# rev11.net
KiCad netlist of a schematic drawn in EAGLE
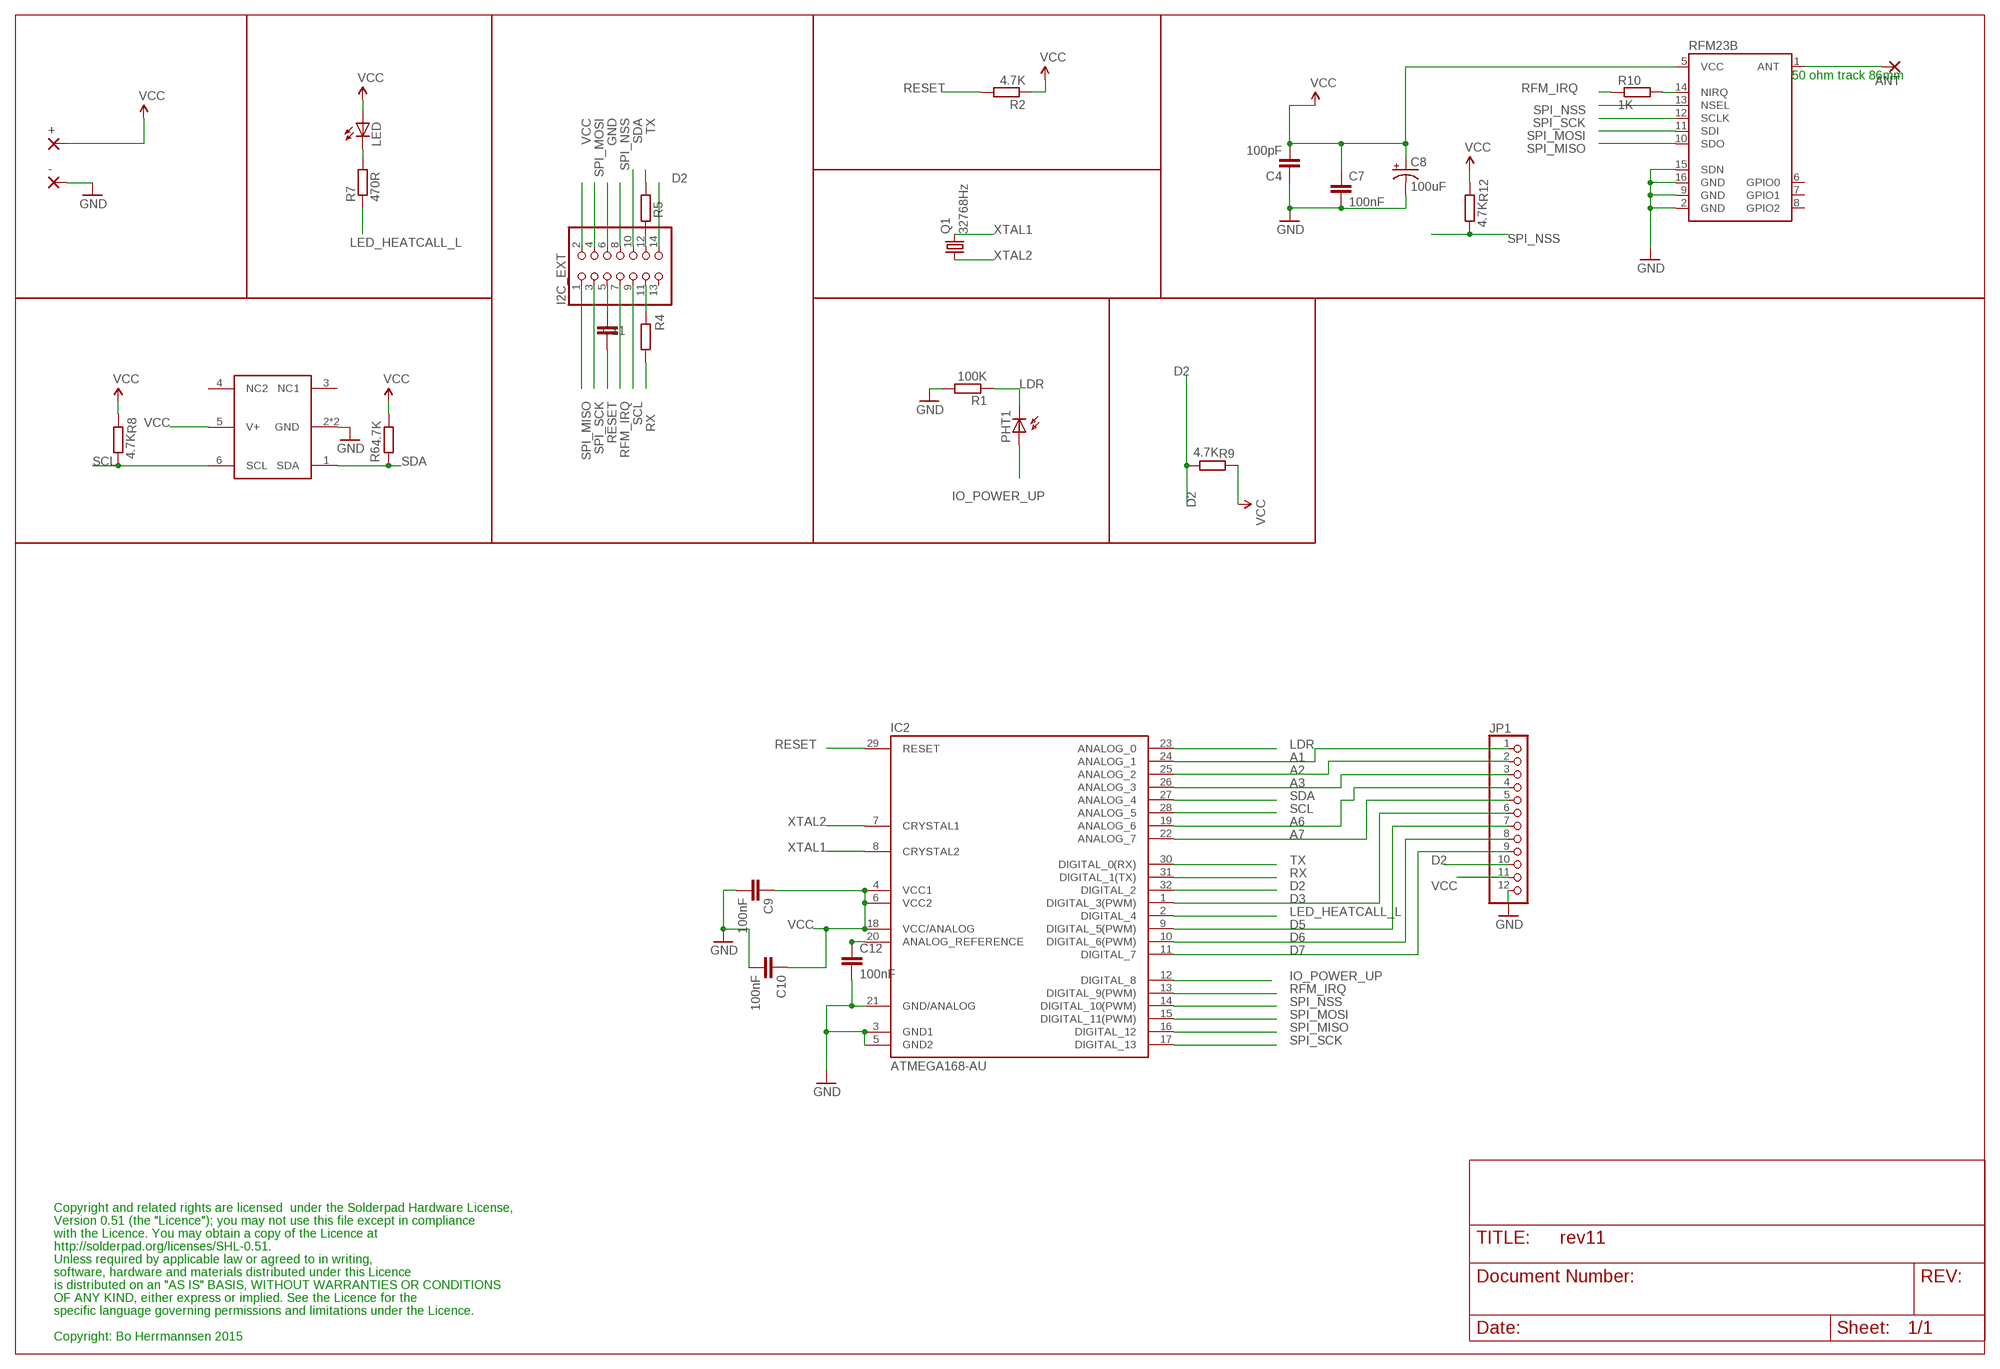
[diagram p0: schematic, sheet 1]

(export (version "E")
  (design (tool "Eeschema 10.0.6"))
  (components
    (comp (ref "+")
      (value "2,15/1,0")
      (footprint "eagle-import:2,15_1,0")
      (libsource (lib "eagle-import") (part "2,15/1,0"))
    )
    (comp (ref "-")
      (value "2,15/1,0")
      (footprint "eagle-import:2,15_1,0")
      (libsource (lib "eagle-import") (part "2,15/1,0"))
    )
    (comp (ref "ANT")
      (value "SMD2")
      (footprint "eagle-import:SMD1,27-2,54")
      (libsource (lib "eagle-import") (part "SMD2"))
    )
    (comp (ref "C4")
      (value "100pF")
      (footprint "eagle-import:C0603")
      (libsource (lib "eagle-import") (part "C-EUC0603"))
    )
    (comp (ref "C7")
      (value "100nF")
      (footprint "eagle-import:C0603")
      (libsource (lib "eagle-import") (part "C-EUC0603"))
    )
    (comp (ref "C8")
      (value "100uF")
      (footprint "eagle-import:EIA3216")
      (libsource (lib "eagle-import") (part "CAP_POL1206"))
    )
    (comp (ref "C9")
      (value "100nF")
      (footprint "eagle-import:C0603")
      (libsource (lib "eagle-import") (part "C-EUC0603"))
    )
    (comp (ref "C10")
      (value "100nF")
      (footprint "eagle-import:C0603")
      (libsource (lib "eagle-import") (part "C-EUC0603"))
    )
    (comp (ref "C11")
      (value "100nF")
      (footprint "eagle-import:C0603")
      (libsource (lib "eagle-import") (part "C-EUC0603"))
    )
    (comp (ref "C12")
      (value "100nF")
      (footprint "eagle-import:C0603")
      (libsource (lib "eagle-import") (part "C-EUC0603"))
    )
    (comp (ref "I2C_EXT")
      (value "PINHD-2X7")
      (footprint "eagle-import:2X07")
      (libsource (lib "eagle-import") (part "PINHD-2X7"))
    )
    (comp (ref "IC2")
      (value "ATMEGA168-AU")
      (footprint "eagle-import:TQFP32-08")
      (libsource (lib "eagle-import") (part "ATMEGA168-AU"))
    )
    (comp (ref "JP1")
      (value "PINHD-1X12")
      (footprint "eagle-import:1X12")
      (libsource (lib "eagle-import") (part "PINHD-1X12"))
    )
    (comp (ref "LED")
      (value "LEDCHIPLED_0603")
      (footprint "eagle-import:CHIPLED_0603")
      (libsource (lib "eagle-import") (part "LEDCHIPLED_0603"))
    )
    (comp (ref "PHT1")
      (value "BPX65")
      (footprint "eagle-import:BPX65")
      (fields (field (name "MPN") "BPX65."))
      (libsource (lib "eagle-import") (part "BPX65"))
    )
    (comp (ref "Q1")
      (value "32768Hz")
      (footprint "eagle-import:MC-306")
      (fields (field (name "MPN") "MC-306 60.0KHZ  100PPM ,12.5PF"))
      (libsource (lib "eagle-import") (part "MC-306"))
    )
    (comp (ref "R1")
      (value "100K")
      (footprint "eagle-import:R0603")
      (libsource (lib "eagle-import") (part "R-EU_R0603"))
    )
    (comp (ref "R2")
      (value "4.7K")
      (footprint "eagle-import:R0603")
      (libsource (lib "eagle-import") (part "R-EU_R0603"))
    )
    (comp (ref "R4")
      (value "4.7K")
      (footprint "eagle-import:R0603")
      (libsource (lib "eagle-import") (part "R-EU_R0603"))
    )
    (comp (ref "R5")
      (value "4.7K")
      (footprint "eagle-import:R0603")
      (libsource (lib "eagle-import") (part "R-EU_R0603"))
    )
    (comp (ref "R6")
      (value "4.7K")
      (footprint "eagle-import:R0603")
      (libsource (lib "eagle-import") (part "R-EU_R0603"))
    )
    (comp (ref "R7")
      (value "470R")
      (footprint "eagle-import:R0603")
      (libsource (lib "eagle-import") (part "R-EU_R0603"))
    )
    (comp (ref "R8")
      (value "4.7K")
      (footprint "eagle-import:R0603")
      (libsource (lib "eagle-import") (part "R-EU_R0603"))
    )
    (comp (ref "R9")
      (value "4.7K")
      (footprint "eagle-import:R0603")
      (libsource (lib "eagle-import") (part "R-EU_R0603"))
    )
    (comp (ref "R10")
      (value "1K")
      (footprint "eagle-import:R0603")
      (libsource (lib "eagle-import") (part "R-EU_R0603"))
    )
    (comp (ref "R12")
      (value "4.7K")
      (footprint "eagle-import:R0603")
      (libsource (lib "eagle-import") (part "R-EU_R0603"))
    )
    (comp (ref "RFM23B")
      (value "RFM23B")
      (footprint "eagle-import:RFM23-XXX-S1")
      (libsource (lib "eagle-import") (part "RFM23B"))
    )
    (comp (ref "U$4")
      (value "SHT21")
      (footprint "eagle-import:SHT21")
      (libsource (lib "eagle-import") (part "SHT21"))
    )
  )
  (nets
    (net (code "1") (name "/A1") (class "Default")
      (node (ref "IC2") (pin "24") (pinfunction "ANALOG_1_24") (pintype "bidirectional"))
      (node (ref "JP1") (pin "1") (pinfunction "1_1") (pintype "passive"))
    )
    (net (code "2") (name "/A2") (class "Default")
      (node (ref "IC2") (pin "25") (pinfunction "ANALOG_2_25") (pintype "bidirectional"))
      (node (ref "JP1") (pin "2") (pinfunction "2_2") (pintype "passive"))
    )
    (net (code "3") (name "/A3") (class "Default")
      (node (ref "IC2") (pin "26") (pinfunction "ANALOG_3_26") (pintype "bidirectional"))
      (node (ref "JP1") (pin "3") (pinfunction "3_3") (pintype "passive"))
    )
    (net (code "4") (name "/A6") (class "Default")
      (node (ref "IC2") (pin "19") (pinfunction "ANALOG_6_19") (pintype "passive"))
      (node (ref "JP1") (pin "4") (pinfunction "4_4") (pintype "passive"))
    )
    (net (code "5") (name "/A7") (class "Default")
      (node (ref "IC2") (pin "22") (pinfunction "ANALOG_7_22") (pintype "passive"))
      (node (ref "JP1") (pin "5") (pinfunction "5_5") (pintype "passive"))
    )
    (net (code "6") (name "/D2") (class "Default")
      (node (ref "I2C_EXT") (pin "14") (pinfunction "14_14") (pintype "passive"))
      (node (ref "IC2") (pin "32") (pinfunction "DIGITAL_2_32") (pintype "bidirectional"))
      (node (ref "JP1") (pin "10") (pinfunction "10_10") (pintype "passive"))
      (node (ref "R9") (pin "1") (pinfunction "1_1") (pintype "passive"))
    )
    (net (code "7") (name "/D3") (class "Default")
      (node (ref "IC2") (pin "1") (pinfunction "DIGITAL_3(PWM)_1") (pintype "bidirectional"))
      (node (ref "JP1") (pin "6") (pinfunction "6_6") (pintype "passive"))
    )
    (net (code "8") (name "/D5") (class "Default")
      (node (ref "IC2") (pin "9") (pinfunction "DIGITAL_5(PWM)_9") (pintype "bidirectional"))
      (node (ref "JP1") (pin "7") (pinfunction "7_7") (pintype "passive"))
    )
    (net (code "9") (name "/D6") (class "Default")
      (node (ref "IC2") (pin "10") (pinfunction "DIGITAL_6(PWM)_10") (pintype "bidirectional"))
      (node (ref "JP1") (pin "8") (pinfunction "8_8") (pintype "passive"))
    )
    (net (code "10") (name "/D7") (class "Default")
      (node (ref "IC2") (pin "11") (pinfunction "DIGITAL_7_11") (pintype "bidirectional"))
      (node (ref "JP1") (pin "9") (pinfunction "9_9") (pintype "passive"))
    )
    (net (code "11") (name "/IO_POWER_UP") (class "Default")
      (node (ref "IC2") (pin "12") (pinfunction "DIGITAL_8_12") (pintype "bidirectional"))
      (node (ref "PHT1") (pin "A") (pinfunction "A_A") (pintype "passive"))
    )
    (net (code "12") (name "/LDR") (class "Default")
      (node (ref "IC2") (pin "23") (pinfunction "ANALOG_0_23") (pintype "bidirectional"))
      (node (ref "PHT1") (pin "K") (pinfunction "C_K") (pintype "passive"))
      (node (ref "R1") (pin "1") (pinfunction "1_1") (pintype "passive"))
    )
    (net (code "13") (name "/LED_HEATCALL_L") (class "Default")
      (node (ref "IC2") (pin "2") (pinfunction "DIGITAL_4_2") (pintype "bidirectional"))
      (node (ref "R7") (pin "1") (pinfunction "1_1") (pintype "passive"))
    )
    (net (code "14") (name "/RESET") (class "Default")
      (node (ref "C11") (pin "1") (pinfunction "1_1") (pintype "passive"))
      (node (ref "IC2") (pin "29") (pinfunction "RESET_29") (pintype "bidirectional"))
      (node (ref "R2") (pin "2") (pinfunction "2_2") (pintype "passive"))
    )
    (net (code "15") (name "/RFM_IRQ") (class "Default")
      (node (ref "I2C_EXT") (pin "7") (pinfunction "7_7") (pintype "passive"))
      (node (ref "IC2") (pin "13") (pinfunction "DIGITAL_9(PWM)_13") (pintype "bidirectional"))
      (node (ref "R10") (pin "1") (pinfunction "1_1") (pintype "passive"))
    )
    (net (code "16") (name "/RX") (class "Default")
      (node (ref "IC2") (pin "31") (pinfunction "DIGITAL_1(TX)_31") (pintype "bidirectional"))
      (node (ref "R4") (pin "1") (pinfunction "1_1") (pintype "passive"))
    )
    (net (code "17") (name "/SCL") (class "Default")
      (node (ref "I2C_EXT") (pin "9") (pinfunction "9_9") (pintype "passive"))
      (node (ref "IC2") (pin "28") (pinfunction "ANALOG_5_28") (pintype "bidirectional"))
      (node (ref "R8") (pin "1") (pinfunction "1_1") (pintype "passive"))
      (node (ref "U$4") (pin "6") (pinfunction "SCL_6") (pintype "bidirectional"))
    )
    (net (code "18") (name "/SDA") (class "Default")
      (node (ref "I2C_EXT") (pin "10") (pinfunction "10_10") (pintype "passive"))
      (node (ref "IC2") (pin "27") (pinfunction "ANALOG_4_27") (pintype "bidirectional"))
      (node (ref "R6") (pin "2") (pinfunction "2_2") (pintype "passive"))
      (node (ref "U$4") (pin "1") (pinfunction "SDA_1") (pintype "bidirectional"))
    )
    (net (code "19") (name "/SPI_MISO") (class "Default")
      (node (ref "I2C_EXT") (pin "1") (pinfunction "1_1") (pintype "passive"))
      (node (ref "IC2") (pin "16") (pinfunction "DIGITAL_12_16") (pintype "bidirectional"))
      (node (ref "RFM23B") (pin "10") (pinfunction "SDO_10") (pintype "output"))
    )
    (net (code "20") (name "/SPI_MOSI") (class "Default")
      (node (ref "I2C_EXT") (pin "4") (pinfunction "4_4") (pintype "passive"))
      (node (ref "IC2") (pin "15") (pinfunction "DIGITAL_11(PWM)_15") (pintype "bidirectional"))
      (node (ref "RFM23B") (pin "11") (pinfunction "SDI_11") (pintype "input"))
    )
    (net (code "21") (name "/SPI_NSS") (class "Default")
      (node (ref "I2C_EXT") (pin "8") (pinfunction "8_8") (pintype "passive"))
      (node (ref "IC2") (pin "14") (pinfunction "DIGITAL_10(PWM)_14") (pintype "bidirectional"))
      (node (ref "R12") (pin "1") (pinfunction "1_1") (pintype "passive"))
      (node (ref "RFM23B") (pin "13") (pinfunction "NSEL_13") (pintype "input"))
    )
    (net (code "22") (name "/SPI_SCK") (class "Default")
      (node (ref "I2C_EXT") (pin "3") (pinfunction "3_3") (pintype "passive"))
      (node (ref "IC2") (pin "17") (pinfunction "DIGITAL_13_17") (pintype "bidirectional"))
      (node (ref "RFM23B") (pin "12") (pinfunction "SCLK_12") (pintype "input"))
    )
    (net (code "23") (name "/TX") (class "Default")
      (node (ref "IC2") (pin "30") (pinfunction "DIGITAL_0(RX)_30") (pintype "bidirectional"))
      (node (ref "R5") (pin "1") (pinfunction "1_1") (pintype "passive"))
    )
    (net (code "24") (name "/XTAL1") (class "Default")
      (node (ref "IC2") (pin "8") (pinfunction "CRYSTAL2_8") (pintype "bidirectional"))
      (node (ref "Q1") (pin "4") (pinfunction "2_4") (pintype "passive"))
    )
    (net (code "25") (name "/XTAL2") (class "Default")
      (node (ref "IC2") (pin "7") (pinfunction "CRYSTAL1_7") (pintype "bidirectional"))
      (node (ref "Q1") (pin "1") (pinfunction "1_1") (pintype "passive"))
    )
    (net (code "26") (name "GND") (class "Default")
      (node (ref "-") (pin "1") (pinfunction "P_1") (pintype "passive"))
      (node (ref "C10") (pin "2") (pinfunction "2_2") (pintype "passive"))
      (node (ref "C12") (pin "2") (pinfunction "2_2") (pintype "passive"))
      (node (ref "C4") (pin "1") (pinfunction "1_1") (pintype "passive"))
      (node (ref "C7") (pin "2") (pinfunction "2_2") (pintype "passive"))
      (node (ref "C8") (pin "C") (pinfunction "-_C") (pintype "passive"))
      (node (ref "C9") (pin "2") (pinfunction "2_2") (pintype "passive"))
      (node (ref "I2C_EXT") (pin "6") (pinfunction "6_6") (pintype "passive"))
      (node (ref "IC2") (pin "21") (pinfunction "GND/ANALOG_21") (pintype "power_in"))
      (node (ref "IC2") (pin "3") (pinfunction "GND1_3") (pintype "power_in"))
      (node (ref "IC2") (pin "5") (pinfunction "GND2_5") (pintype "power_in"))
      (node (ref "JP1") (pin "12") (pinfunction "12_12") (pintype "passive"))
      (node (ref "R1") (pin "2") (pinfunction "2_2") (pintype "passive"))
      (node (ref "RFM23B") (pin "15") (pinfunction "SDN_15") (pintype "input"))
      (node (ref "RFM23B") (pin "16") (pinfunction "GND_16") (pintype "power_in"))
      (node (ref "RFM23B") (pin "2") (pinfunction "GND_2") (pintype "power_in"))
      (node (ref "RFM23B") (pin "9") (pinfunction "GND_9") (pintype "power_in"))
      (node (ref "U$4") (pin "2") (pinfunction "GND_2") (pintype "bidirectional"))
      (node (ref "U$4") (pin "P$1") (pinfunction "GND_P$1") (pintype "bidirectional"))
    )
    (net (code "27") (name "Net-(ANT-P)") (class "Default")
      (node (ref "ANT") (pin "1") (pinfunction "P_1") (pintype "passive"))
      (node (ref "RFM23B") (pin "1") (pinfunction "ANT_1") (pintype "bidirectional"))
    )
    (net (code "28") (name "Net-(C11-Pad2)") (class "Default")
      (node (ref "C11") (pin "2") (pinfunction "2_2") (pintype "passive"))
      (node (ref "I2C_EXT") (pin "5") (pinfunction "5_5") (pintype "passive"))
    )
    (net (code "29") (name "Net-(I2C_EXT-Pad11)") (class "Default")
      (node (ref "I2C_EXT") (pin "11") (pinfunction "11_11") (pintype "passive"))
      (node (ref "R4") (pin "2") (pinfunction "2_2") (pintype "passive"))
    )
    (net (code "30") (name "Net-(I2C_EXT-Pad12)") (class "Default")
      (node (ref "I2C_EXT") (pin "12") (pinfunction "12_12") (pintype "passive"))
      (node (ref "R5") (pin "2") (pinfunction "2_2") (pintype "passive"))
    )
    (net (code "31") (name "Net-(IC2-ANALOG_REFERENCE)") (class "Default")
      (node (ref "C12") (pin "1") (pinfunction "1_1") (pintype "passive"))
      (node (ref "IC2") (pin "20") (pinfunction "ANALOG_REFERENCE_20") (pintype "passive"))
    )
    (net (code "32") (name "Net-(LED-PadC)") (class "Default")
      (node (ref "LED") (pin "C") (pinfunction "C_C") (pintype "passive"))
      (node (ref "R7") (pin "2") (pinfunction "2_2") (pintype "passive"))
    )
    (net (code "33") (name "Net-(RFM23B-NIRQ)") (class "Default")
      (node (ref "R10") (pin "2") (pinfunction "2_2") (pintype "passive"))
      (node (ref "RFM23B") (pin "14") (pinfunction "NIRQ_14") (pintype "output"))
    )
    (net (code "34") (name "VCC") (class "Default")
      (node (ref "+") (pin "1") (pinfunction "P_1") (pintype "passive"))
      (node (ref "C10") (pin "1") (pinfunction "1_1") (pintype "passive"))
      (node (ref "C4") (pin "2") (pinfunction "2_2") (pintype "passive"))
      (node (ref "C7") (pin "1") (pinfunction "1_1") (pintype "passive"))
      (node (ref "C8") (pin "A") (pinfunction "+_A") (pintype "passive"))
      (node (ref "C9") (pin "1") (pinfunction "1_1") (pintype "passive"))
      (node (ref "I2C_EXT") (pin "2") (pinfunction "2_2") (pintype "passive"))
      (node (ref "IC2") (pin "18") (pinfunction "VCC/ANALOG_18") (pintype "passive"))
      (node (ref "IC2") (pin "4") (pinfunction "VCC1_4") (pintype "power_in"))
      (node (ref "IC2") (pin "6") (pinfunction "VCC2_6") (pintype "power_in"))
      (node (ref "JP1") (pin "11") (pinfunction "11_11") (pintype "passive"))
      (node (ref "LED") (pin "A") (pinfunction "A_A") (pintype "passive"))
      (node (ref "R12") (pin "2") (pinfunction "2_2") (pintype "passive"))
      (node (ref "R2") (pin "1") (pinfunction "1_1") (pintype "passive"))
      (node (ref "R6") (pin "1") (pinfunction "1_1") (pintype "passive"))
      (node (ref "R8") (pin "2") (pinfunction "2_2") (pintype "passive"))
      (node (ref "R9") (pin "2") (pinfunction "2_2") (pintype "passive"))
      (node (ref "RFM23B") (pin "5") (pinfunction "VCC_5") (pintype "bidirectional"))
      (node (ref "U$4") (pin "5") (pinfunction "V+_5") (pintype "bidirectional"))
    )
    (net (code "35") (name "unconnected-(I2C_EXT-Pad13)") (class "Default")
      (node (ref "I2C_EXT") (pin "13") (pinfunction "13_13") (pintype "passive"))
    )
    (net (code "36") (name "unconnected-(RFM23B-GPIO0-Pad6)") (class "Default")
      (node (ref "RFM23B") (pin "6") (pinfunction "GPIO0_6") (pintype "bidirectional"))
    )
    (net (code "37") (name "unconnected-(RFM23B-GPIO1-Pad7)") (class "Default")
      (node (ref "RFM23B") (pin "7") (pinfunction "GPIO1_7") (pintype "bidirectional"))
    )
    (net (code "38") (name "unconnected-(RFM23B-GPIO2-Pad8)") (class "Default")
      (node (ref "RFM23B") (pin "8") (pinfunction "GPIO2_8") (pintype "bidirectional"))
    )
    (net (code "39") (name "unconnected-(U$4-NC1-Pad3)") (class "Default")
      (node (ref "U$4") (pin "3") (pinfunction "NC1_3") (pintype "bidirectional"))
    )
    (net (code "40") (name "unconnected-(U$4-NC2-Pad4)") (class "Default")
      (node (ref "U$4") (pin "4") (pinfunction "NC2_4") (pintype "bidirectional"))
    )
  )
)
